# CrackberryPi_1_0_6_3_power.net
KiCad netlist of a schematic drawn in EAGLE
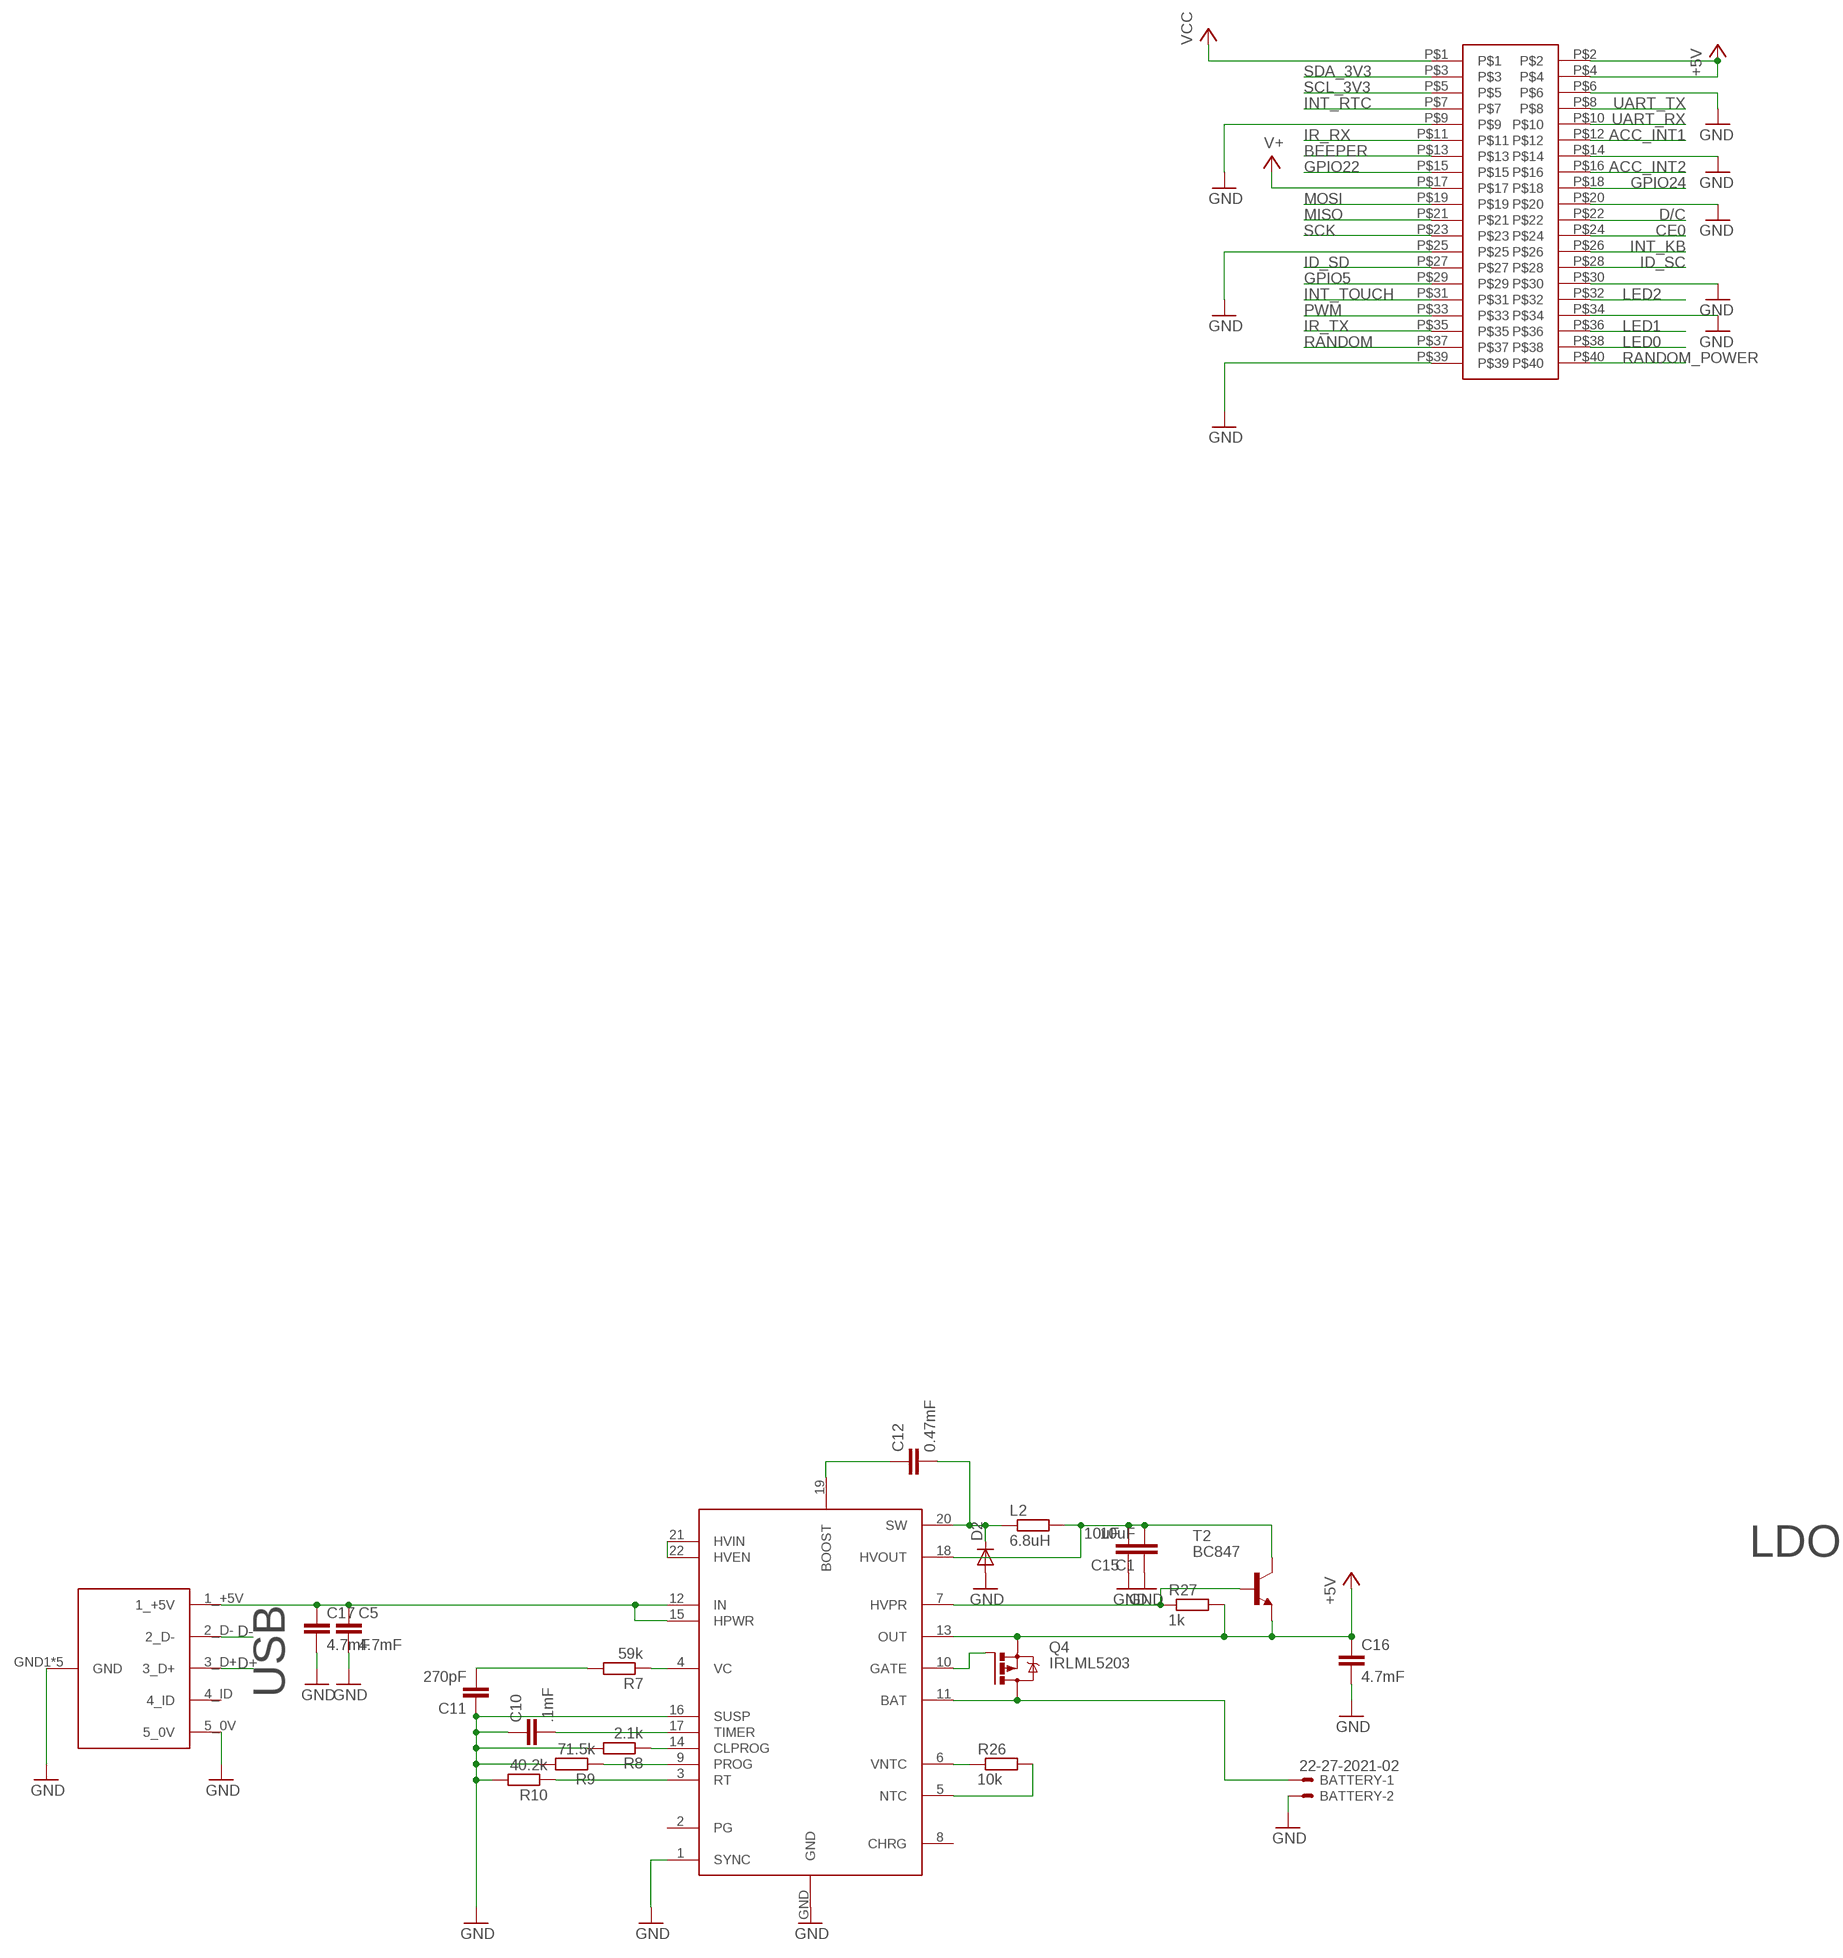
[diagram p0: schematic, sheet 1]

(export (version "E")
  (design (tool "Eeschema 10.0.6"))
  (components
    (comp (ref "BATTERY")
      (value "22-27-2021-02")
      (footprint "eagle-import:6410-02")
      (libsource (lib "eagle-import") (part "22-?-0227-2021"))
    )
    (comp (ref "C1")
      (value "10uF")
      (footprint "eagle-import:C0603")
      (libsource (lib "eagle-import") (part "C-EUC0603"))
    )
    (comp (ref "C5")
      (value "4.7mF")
      (footprint "eagle-import:C0603")
      (libsource (lib "eagle-import") (part "C-EUC0603"))
    )
    (comp (ref "C10")
      (value ".1mF")
      (footprint "eagle-import:C0603")
      (libsource (lib "eagle-import") (part "C-EUC0603"))
    )
    (comp (ref "C11")
      (value "270pF")
      (footprint "eagle-import:C0603")
      (libsource (lib "eagle-import") (part "C-EUC0603"))
    )
    (comp (ref "C12")
      (value "0.47mF")
      (footprint "eagle-import:C0603")
      (libsource (lib "eagle-import") (part "C-EUC0603"))
    )
    (comp (ref "C15")
      (value "10uF")
      (footprint "eagle-import:C0603")
      (libsource (lib "eagle-import") (part "C-EUC0603"))
    )
    (comp (ref "C16")
      (value "4.7mF")
      (footprint "eagle-import:C0603")
      (libsource (lib "eagle-import") (part "C-EUC0603"))
    )
    (comp (ref "C17")
      (value "4.7mF")
      (footprint "eagle-import:C0603")
      (libsource (lib "eagle-import") (part "C-EUC0603"))
    )
    (comp (ref "D2")
      (value "DIODE-SOD123")
      (footprint "eagle-import:SOD123")
      (libsource (lib "eagle-import") (part "DIODE-SOD123"))
    )
    (comp (ref "L2")
      (value "6.8uH")
      (footprint "eagle-import:R2010")
      (libsource (lib "eagle-import") (part "R-EU_R2010"))
    )
    (comp (ref "Q4")
      (value "IRLML5203")
      (footprint "eagle-import:MICRO3")
      (libsource (lib "eagle-import") (part "IRLML5203"))
    )
    (comp (ref "R7")
      (value "59k")
      (footprint "eagle-import:R0603")
      (libsource (lib "eagle-import") (part "R-EU_R0603"))
    )
    (comp (ref "R8")
      (value "2.1k")
      (footprint "eagle-import:R0603")
      (libsource (lib "eagle-import") (part "R-EU_R0603"))
    )
    (comp (ref "R9")
      (value "71.5k")
      (footprint "eagle-import:R0603")
      (libsource (lib "eagle-import") (part "R-EU_R0603"))
    )
    (comp (ref "R10")
      (value "40.2k")
      (footprint "eagle-import:R0603")
      (libsource (lib "eagle-import") (part "R-EU_R0603"))
    )
    (comp (ref "R26")
      (value "10k")
      (footprint "eagle-import:R0603")
      (libsource (lib "eagle-import") (part "R-EU_R0603"))
    )
    (comp (ref "R27")
      (value "1k")
      (footprint "eagle-import:R0603")
      (libsource (lib "eagle-import") (part "R-EU_R0603"))
    )
    (comp (ref "T2")
      (value "BC847")
      (footprint "eagle-import:SOT23")
      (libsource (lib "eagle-import") (part "BC847"))
    )
    (comp (ref "U$1")
      (value "LTC4090")
      (footprint "eagle-import:DFN22")
      (libsource (lib "eagle-import") (part "LTC4090"))
    )
    (comp (ref "U$9")
      (value "MICRO_USB")
      (footprint "eagle-import:MICRO_USB")
      (libsource (lib "eagle-import") (part "MICRO_USB"))
    )
    (comp (ref "U$11")
      (value "HEADER")
      (footprint "eagle-import:20X2")
      (libsource (lib "eagle-import") (part "HEADER"))
    )
  )
  (nets
    (net (code "1") (name "+5V") (class "Default")
      (node (ref "C16") (pin "1") (pinfunction "1_1") (pintype "passive"))
      (node (ref "Q4") (pin "2") (pinfunction "S_2") (pintype "passive"))
      (node (ref "R27") (pin "2") (pinfunction "2_2") (pintype "passive"))
      (node (ref "T2") (pin "2") (pinfunction "E_2") (pintype "passive"))
      (node (ref "U$1") (pin "13") (pinfunction "OUT_13") (pintype "bidirectional"))
      (node (ref "U$11") (pin "P$2") (pinfunction "P$2_P$2") (pintype "bidirectional"))
      (node (ref "U$11") (pin "P$4") (pinfunction "P$4_P$4") (pintype "bidirectional"))
    )
    (net (code "2") (name "/ACC_INT1") (class "Default")
      (node (ref "U$11") (pin "P$12") (pinfunction "P$12_P$12") (pintype "bidirectional"))
    )
    (net (code "3") (name "/ACC_INT2") (class "Default")
      (node (ref "U$11") (pin "P$16") (pinfunction "P$16_P$16") (pintype "bidirectional"))
    )
    (net (code "4") (name "/BEEPER") (class "Default")
      (node (ref "U$11") (pin "P$13") (pinfunction "P$13_P$13") (pintype "bidirectional"))
    )
    (net (code "5") (name "/CE0") (class "Default")
      (node (ref "U$11") (pin "P$24") (pinfunction "P$24_P$24") (pintype "bidirectional"))
    )
    (net (code "6") (name "/D+") (class "Default")
      (node (ref "U$9") (pin "3_D+") (pinfunction "3_D+_3_D+") (pintype "bidirectional"))
    )
    (net (code "7") (name "/D-") (class "Default")
      (node (ref "U$9") (pin "2_D-") (pinfunction "2_D-_2_D-") (pintype "bidirectional"))
    )
    (net (code "8") (name "/D{slash}C") (class "Default")
      (node (ref "U$11") (pin "P$22") (pinfunction "P$22_P$22") (pintype "bidirectional"))
    )
    (net (code "9") (name "/GPIO5") (class "Default")
      (node (ref "U$11") (pin "P$29") (pinfunction "P$29_P$29") (pintype "bidirectional"))
    )
    (net (code "10") (name "/GPIO22") (class "Default")
      (node (ref "U$11") (pin "P$15") (pinfunction "P$15_P$15") (pintype "bidirectional"))
    )
    (net (code "11") (name "/GPIO24") (class "Default")
      (node (ref "U$11") (pin "P$18") (pinfunction "P$18_P$18") (pintype "bidirectional"))
    )
    (net (code "12") (name "/ID_SC") (class "Default")
      (node (ref "U$11") (pin "P$28") (pinfunction "P$28_P$28") (pintype "bidirectional"))
    )
    (net (code "13") (name "/ID_SD") (class "Default")
      (node (ref "U$11") (pin "P$27") (pinfunction "P$27_P$27") (pintype "bidirectional"))
    )
    (net (code "14") (name "/INT_KB") (class "Default")
      (node (ref "U$11") (pin "P$26") (pinfunction "P$26_P$26") (pintype "bidirectional"))
    )
    (net (code "15") (name "/INT_RTC") (class "Default")
      (node (ref "U$11") (pin "P$7") (pinfunction "P$7_P$7") (pintype "bidirectional"))
    )
    (net (code "16") (name "/INT_TOUCH") (class "Default")
      (node (ref "U$11") (pin "P$31") (pinfunction "P$31_P$31") (pintype "bidirectional"))
    )
    (net (code "17") (name "/IR_RX") (class "Default")
      (node (ref "U$11") (pin "P$11") (pinfunction "P$11_P$11") (pintype "bidirectional"))
    )
    (net (code "18") (name "/IR_TX") (class "Default")
      (node (ref "U$11") (pin "P$35") (pinfunction "P$35_P$35") (pintype "bidirectional"))
    )
    (net (code "19") (name "/LED0") (class "Default")
      (node (ref "U$11") (pin "P$38") (pinfunction "P$38_P$38") (pintype "bidirectional"))
    )
    (net (code "20") (name "/LED1") (class "Default")
      (node (ref "U$11") (pin "P$36") (pinfunction "P$36_P$36") (pintype "bidirectional"))
    )
    (net (code "21") (name "/LED2") (class "Default")
      (node (ref "U$11") (pin "P$32") (pinfunction "P$32_P$32") (pintype "bidirectional"))
    )
    (net (code "22") (name "/MISO") (class "Default")
      (node (ref "U$11") (pin "P$21") (pinfunction "P$21_P$21") (pintype "bidirectional"))
    )
    (net (code "23") (name "/MOSI") (class "Default")
      (node (ref "U$11") (pin "P$19") (pinfunction "P$19_P$19") (pintype "bidirectional"))
    )
    (net (code "24") (name "/PWM") (class "Default")
      (node (ref "U$11") (pin "P$33") (pinfunction "P$33_P$33") (pintype "bidirectional"))
    )
    (net (code "25") (name "/RANDOM") (class "Default")
      (node (ref "U$11") (pin "P$37") (pinfunction "P$37_P$37") (pintype "bidirectional"))
    )
    (net (code "26") (name "/RANDOM_POWER") (class "Default")
      (node (ref "U$11") (pin "P$40") (pinfunction "P$40_P$40") (pintype "bidirectional"))
    )
    (net (code "27") (name "/SCK") (class "Default")
      (node (ref "U$11") (pin "P$23") (pinfunction "P$23_P$23") (pintype "bidirectional"))
    )
    (net (code "28") (name "/SCL_3V3") (class "Default")
      (node (ref "U$11") (pin "P$5") (pinfunction "P$5_P$5") (pintype "bidirectional"))
    )
    (net (code "29") (name "/SDA_3V3") (class "Default")
      (node (ref "U$11") (pin "P$3") (pinfunction "P$3_P$3") (pintype "bidirectional"))
    )
    (net (code "30") (name "/UART_RX") (class "Default")
      (node (ref "U$11") (pin "P$10") (pinfunction "P$10_P$10") (pintype "bidirectional"))
    )
    (net (code "31") (name "/UART_TX") (class "Default")
      (node (ref "U$11") (pin "P$8") (pinfunction "P$8_P$8") (pintype "bidirectional"))
    )
    (net (code "32") (name "GND") (class "Default")
      (node (ref "BATTERY") (pin "2") (pinfunction "S_2") (pintype "passive"))
      (node (ref "C1") (pin "1") (pinfunction "1_1") (pintype "passive"))
      (node (ref "C10") (pin "1") (pinfunction "1_1") (pintype "passive"))
      (node (ref "C11") (pin "1") (pinfunction "1_1") (pintype "passive"))
      (node (ref "C15") (pin "1") (pinfunction "1_1") (pintype "passive"))
      (node (ref "C16") (pin "2") (pinfunction "2_2") (pintype "passive"))
      (node (ref "C17") (pin "2") (pinfunction "2_2") (pintype "passive"))
      (node (ref "C5") (pin "2") (pinfunction "2_2") (pintype "passive"))
      (node (ref "D2") (pin "A") (pinfunction "A_A") (pintype "passive"))
      (node (ref "R10") (pin "2") (pinfunction "2_2") (pintype "passive"))
      (node (ref "R8") (pin "2") (pinfunction "2_2") (pintype "passive"))
      (node (ref "R9") (pin "2") (pinfunction "2_2") (pintype "passive"))
      (node (ref "U$1") (pin "1") (pinfunction "SYNC_1") (pintype "bidirectional"))
      (node (ref "U$1") (pin "16") (pinfunction "SUSP_16") (pintype "bidirectional"))
      (node (ref "U$1") (pin "GND") (pinfunction "GND_GND") (pintype "bidirectional"))
      (node (ref "U$11") (pin "P$14") (pinfunction "P$14_P$14") (pintype "bidirectional"))
      (node (ref "U$11") (pin "P$20") (pinfunction "P$20_P$20") (pintype "bidirectional"))
      (node (ref "U$11") (pin "P$25") (pinfunction "P$25_P$25") (pintype "bidirectional"))
      (node (ref "U$11") (pin "P$30") (pinfunction "P$30_P$30") (pintype "bidirectional"))
      (node (ref "U$11") (pin "P$34") (pinfunction "P$34_P$34") (pintype "bidirectional"))
      (node (ref "U$11") (pin "P$39") (pinfunction "P$39_P$39") (pintype "bidirectional"))
      (node (ref "U$11") (pin "P$6") (pinfunction "P$6_P$6") (pintype "bidirectional"))
      (node (ref "U$11") (pin "P$9") (pinfunction "P$9_P$9") (pintype "bidirectional"))
      (node (ref "U$9") (pin "5_0V") (pinfunction "5_0V_5_0V") (pintype "bidirectional"))
      (node (ref "U$9") (pin "GND1") (pinfunction "GND_GND1") (pintype "bidirectional"))
      (node (ref "U$9") (pin "GND2") (pinfunction "GND_GND2") (pintype "bidirectional"))
      (node (ref "U$9") (pin "GND5") (pinfunction "GND_GND5") (pintype "bidirectional"))
      (node (ref "U$9") (pin "P$1") (pinfunction "GND_P$1") (pintype "bidirectional"))
      (node (ref "U$9") (pin "P$7") (pinfunction "GND_P$7") (pintype "bidirectional"))
    )
    (net (code "33") (name "Net-(BATTERYA-S)") (class "Default")
      (node (ref "BATTERY") (pin "1") (pinfunction "S_1") (pintype "passive"))
      (node (ref "Q4") (pin "3") (pinfunction "D_3") (pintype "passive"))
      (node (ref "U$1") (pin "11") (pinfunction "BAT_11") (pintype "bidirectional"))
    )
    (net (code "34") (name "Net-(C11-Pad2)") (class "Default")
      (node (ref "C11") (pin "2") (pinfunction "2_2") (pintype "passive"))
      (node (ref "R7") (pin "2") (pinfunction "2_2") (pintype "passive"))
    )
    (net (code "35") (name "Net-(Q4-G)") (class "Default")
      (node (ref "Q4") (pin "1") (pinfunction "G_1") (pintype "passive"))
      (node (ref "U$1") (pin "10") (pinfunction "GATE_10") (pintype "bidirectional"))
    )
    (net (code "36") (name "Net-(T2-B)") (class "Default")
      (node (ref "R27") (pin "1") (pinfunction "1_1") (pintype "passive"))
      (node (ref "T2") (pin "1") (pinfunction "B_1") (pintype "passive"))
      (node (ref "U$1") (pin "7") (pinfunction "HVPR_7") (pintype "bidirectional"))
    )
    (net (code "37") (name "Net-(T2-C)") (class "Default")
      (node (ref "C1") (pin "2") (pinfunction "2_2") (pintype "passive"))
      (node (ref "C15") (pin "2") (pinfunction "2_2") (pintype "passive"))
      (node (ref "L2") (pin "2") (pinfunction "2_2") (pintype "passive"))
      (node (ref "T2") (pin "3") (pinfunction "C_3") (pintype "passive"))
      (node (ref "U$1") (pin "18") (pinfunction "HVOUT_18") (pintype "bidirectional"))
    )
    (net (code "38") (name "Net-(U$1-BOOST)") (class "Default")
      (node (ref "C12") (pin "1") (pinfunction "1_1") (pintype "passive"))
      (node (ref "U$1") (pin "19") (pinfunction "BOOST_19") (pintype "bidirectional"))
    )
    (net (code "39") (name "Net-(U$1-CLPROG)") (class "Default")
      (node (ref "R8") (pin "1") (pinfunction "1_1") (pintype "passive"))
      (node (ref "U$1") (pin "14") (pinfunction "CLPROG_14") (pintype "bidirectional"))
    )
    (net (code "40") (name "Net-(U$1-HPWR)") (class "Default")
      (node (ref "C17") (pin "1") (pinfunction "1_1") (pintype "passive"))
      (node (ref "C5") (pin "1") (pinfunction "1_1") (pintype "passive"))
      (node (ref "U$1") (pin "12") (pinfunction "IN_12") (pintype "bidirectional"))
      (node (ref "U$1") (pin "15") (pinfunction "HPWR_15") (pintype "bidirectional"))
      (node (ref "U$9") (pin "1_+5V") (pinfunction "1_+5V_1_+5V") (pintype "bidirectional"))
    )
    (net (code "41") (name "Net-(U$1-HVEN)") (class "Default")
      (node (ref "U$1") (pin "21") (pinfunction "HVIN_21") (pintype "bidirectional"))
      (node (ref "U$1") (pin "22") (pinfunction "HVEN_22") (pintype "bidirectional"))
    )
    (net (code "42") (name "Net-(U$1-NTC)") (class "Default")
      (node (ref "R26") (pin "2") (pinfunction "2_2") (pintype "passive"))
      (node (ref "U$1") (pin "5") (pinfunction "NTC_5") (pintype "bidirectional"))
    )
    (net (code "43") (name "Net-(U$1-PROG)") (class "Default")
      (node (ref "R9") (pin "1") (pinfunction "1_1") (pintype "passive"))
      (node (ref "U$1") (pin "9") (pinfunction "PROG_9") (pintype "bidirectional"))
    )
    (net (code "44") (name "Net-(U$1-RT)") (class "Default")
      (node (ref "R10") (pin "1") (pinfunction "1_1") (pintype "passive"))
      (node (ref "U$1") (pin "3") (pinfunction "RT_3") (pintype "bidirectional"))
    )
    (net (code "45") (name "Net-(U$1-SW)") (class "Default")
      (node (ref "C12") (pin "2") (pinfunction "2_2") (pintype "passive"))
      (node (ref "D2") (pin "C") (pinfunction "C_C") (pintype "passive"))
      (node (ref "L2") (pin "1") (pinfunction "1_1") (pintype "passive"))
      (node (ref "U$1") (pin "20") (pinfunction "SW_20") (pintype "bidirectional"))
    )
    (net (code "46") (name "Net-(U$1-TIMER)") (class "Default")
      (node (ref "C10") (pin "2") (pinfunction "2_2") (pintype "passive"))
      (node (ref "U$1") (pin "17") (pinfunction "TIMER_17") (pintype "bidirectional"))
    )
    (net (code "47") (name "Net-(U$1-VC)") (class "Default")
      (node (ref "R7") (pin "1") (pinfunction "1_1") (pintype "passive"))
      (node (ref "U$1") (pin "4") (pinfunction "VC_4") (pintype "bidirectional"))
    )
    (net (code "48") (name "Net-(U$1-VNTC)") (class "Default")
      (node (ref "R26") (pin "1") (pinfunction "1_1") (pintype "passive"))
      (node (ref "U$1") (pin "6") (pinfunction "VNTC_6") (pintype "bidirectional"))
    )
    (net (code "49") (name "V+") (class "Default")
      (node (ref "U$11") (pin "P$17") (pinfunction "P$17_P$17") (pintype "bidirectional"))
    )
    (net (code "50") (name "VCC") (class "Default")
      (node (ref "U$11") (pin "P$1") (pinfunction "P$1_P$1") (pintype "bidirectional"))
    )
    (net (code "51") (name "unconnected-(U$1-CHRG-Pad8)") (class "Default")
      (node (ref "U$1") (pin "8") (pinfunction "CHRG_8") (pintype "bidirectional"))
    )
    (net (code "52") (name "unconnected-(U$1-PG-Pad2)") (class "Default")
      (node (ref "U$1") (pin "2") (pinfunction "PG_2") (pintype "bidirectional"))
    )
    (net (code "53") (name "unconnected-(U$9-Pad4_ID)") (class "Default")
      (node (ref "U$9") (pin "4_ID") (pinfunction "4_ID_4_ID") (pintype "bidirectional"))
    )
  )
)
